# Liquid_Tremolo.net
KiCad netlist of a schematic drawn in Altium Designer
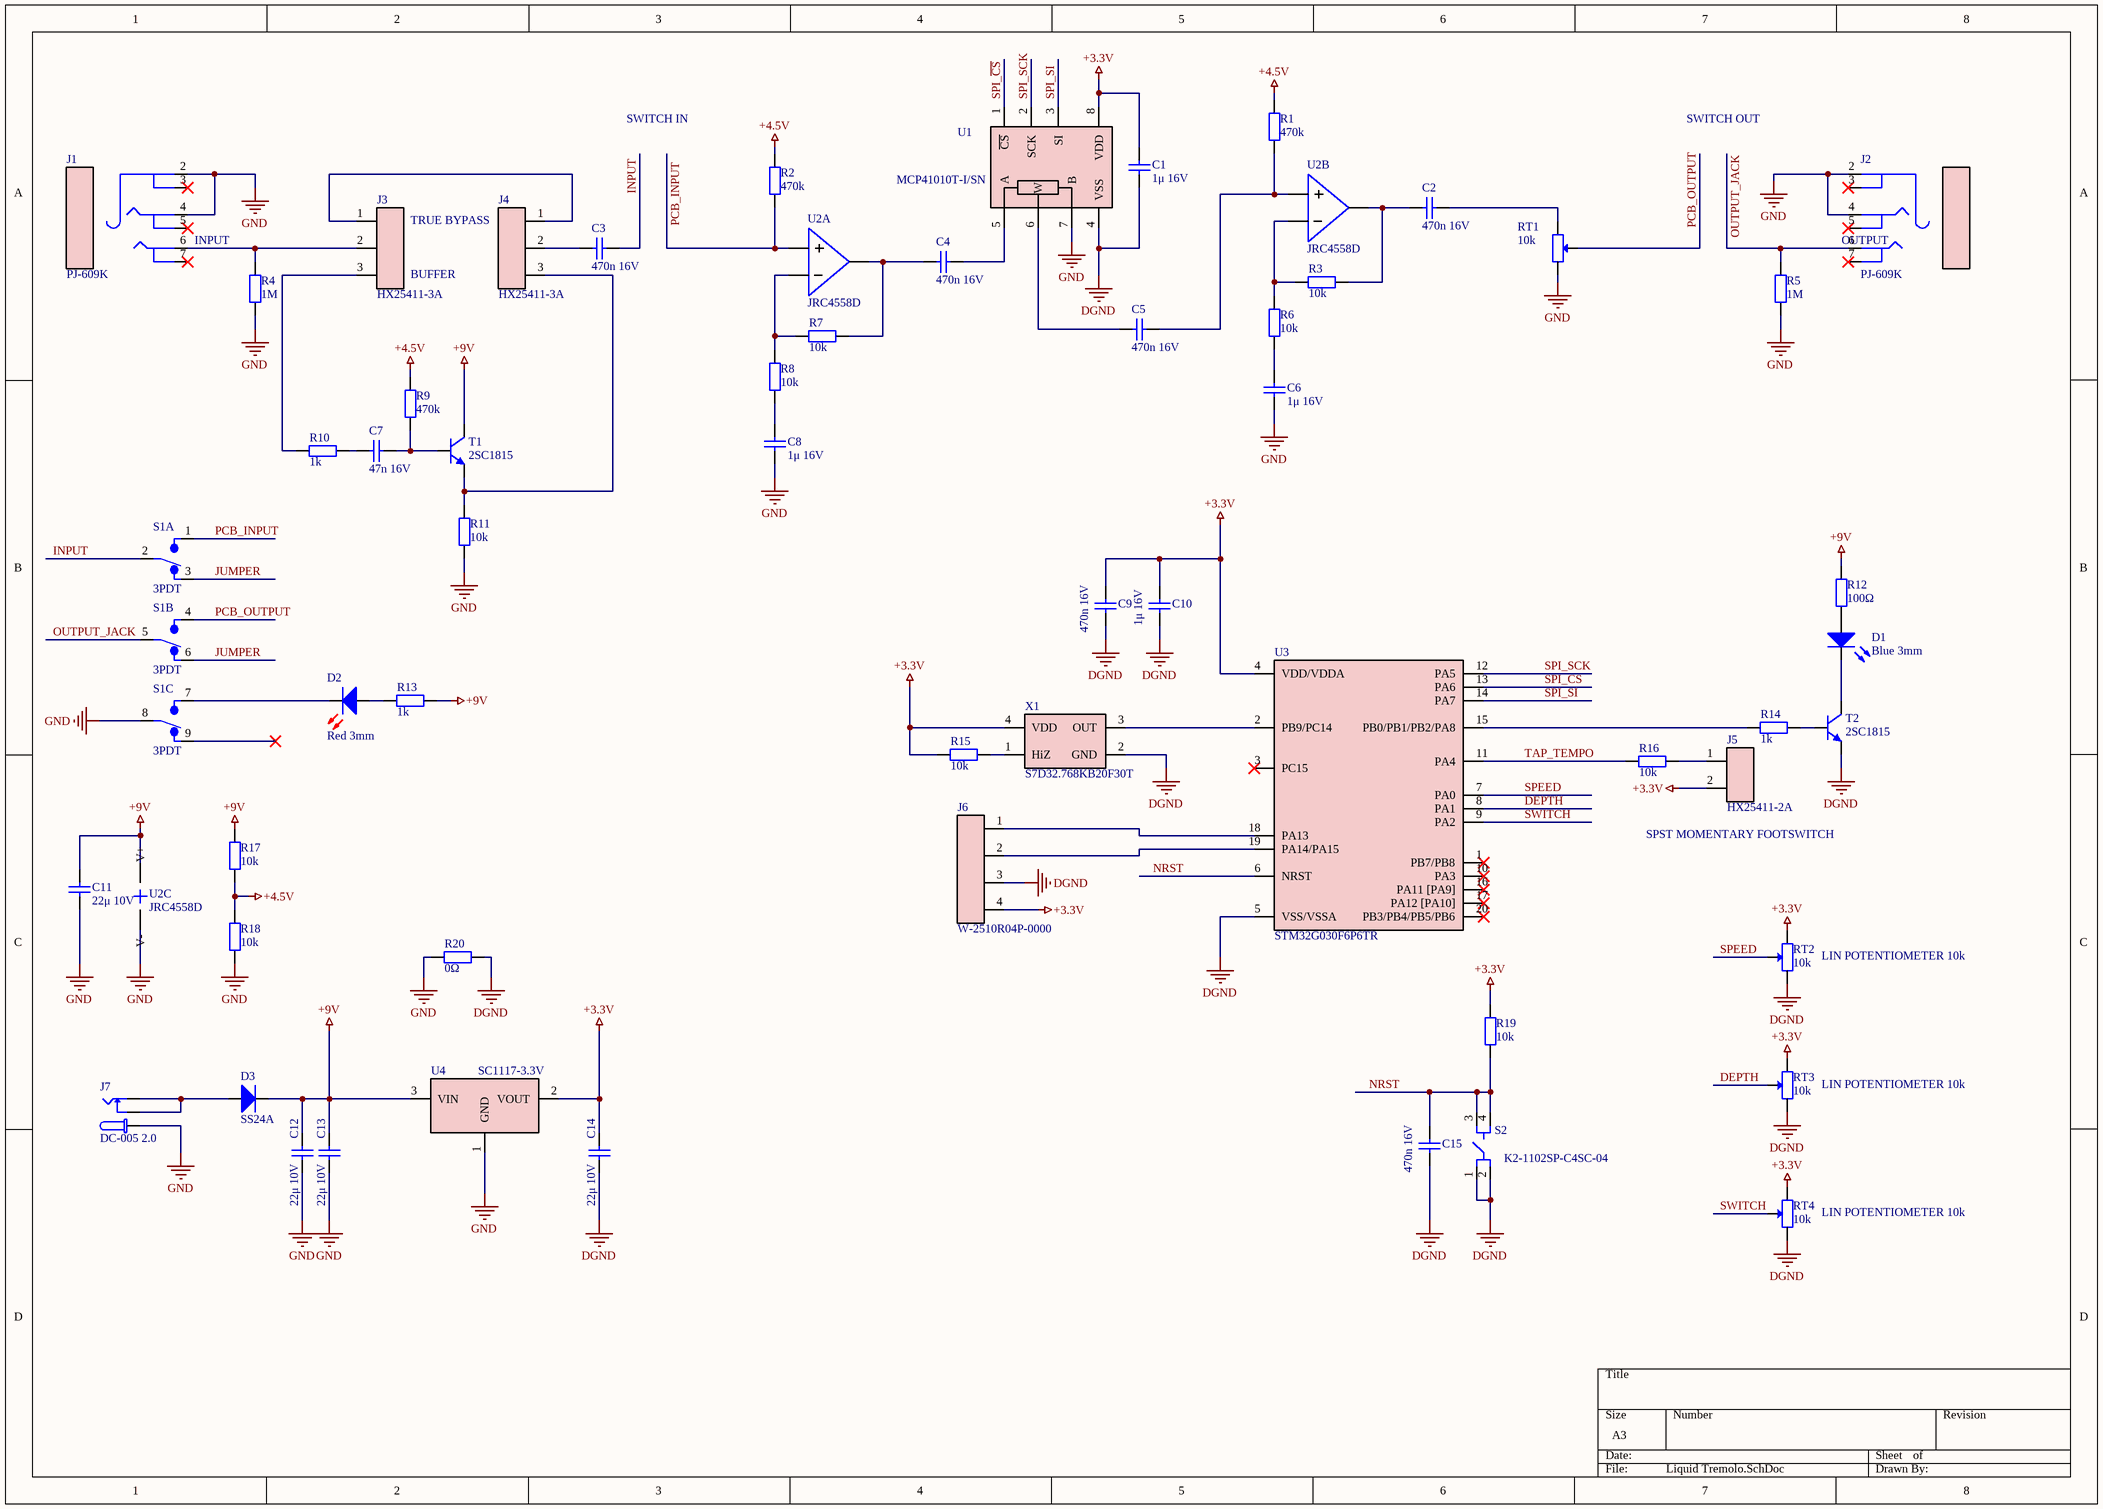
[diagram p0: Liquid Tremolo.SchDoc]

(export (version "E")
  (design (tool "Eeschema 10.0.6"))
  (components
    (comp (ref "C1")
      (value "1μ 16V")
      (footprint "Liquid Tremolo:Capacitor 0603")
      (description "X7R ±10% 1uF 16V 0603 Multilayer Ceramic Capacitors MLCC - SMD/SMT ROHS")
      (fields (field (name "MFR. PART #") "CC0603KRX7R7BB105") (field (name "LCSC PART #") "C106248"))
      (libsource (lib "Liquid Tremolo") (part "Capacitor 1μF 0603 ±10% 16V"))
    )
    (comp (ref "C2")
      (value "470n 16V")
      (footprint "Liquid Tremolo:Capacitor 0603")
      (description "X7R ±10% 470nF 16V 0603 Multilayer Ceramic Capacitors MLCC - SMD/SMT ROHS")
      (fields (field (name "MFR. PART #") "CC0603KRX7R7BB474") (field (name "LCSC PART #") "C106851"))
      (libsource (lib "Liquid Tremolo") (part "Capacitor 470nF 0603 ±10% 16V"))
    )
    (comp (ref "C3")
      (value "470n 16V")
      (footprint "Liquid Tremolo:Capacitor 0603")
      (description "X7R ±10% 470nF 16V 0603 Multilayer Ceramic Capacitors MLCC - SMD/SMT ROHS")
      (fields (field (name "MFR. PART #") "CC0603KRX7R7BB474") (field (name "LCSC PART #") "C106851"))
      (libsource (lib "Liquid Tremolo") (part "Capacitor 470nF 0603 ±10% 16V"))
    )
    (comp (ref "C4")
      (value "470n 16V")
      (footprint "Liquid Tremolo:Capacitor 0603")
      (description "X7R ±10% 470nF 16V 0603 Multilayer Ceramic Capacitors MLCC - SMD/SMT ROHS")
      (fields (field (name "MFR. PART #") "CC0603KRX7R7BB474") (field (name "LCSC PART #") "C106851"))
      (libsource (lib "Liquid Tremolo") (part "Capacitor 470nF 0603 ±10% 16V"))
    )
    (comp (ref "C5")
      (value "470n 16V")
      (footprint "Liquid Tremolo:Capacitor 0603")
      (description "X7R ±10% 470nF 16V 0603 Multilayer Ceramic Capacitors MLCC - SMD/SMT ROHS")
      (fields (field (name "MFR. PART #") "CC0603KRX7R7BB474") (field (name "LCSC PART #") "C106851"))
      (libsource (lib "Liquid Tremolo") (part "Capacitor 470nF 0603 ±10% 16V"))
    )
    (comp (ref "C6")
      (value "1μ 16V")
      (footprint "Liquid Tremolo:Capacitor 0603")
      (description "X7R ±10% 1uF 16V 0603 Multilayer Ceramic Capacitors MLCC - SMD/SMT ROHS")
      (fields (field (name "MFR. PART #") "CC0603KRX7R7BB105") (field (name "LCSC PART #") "C106248"))
      (libsource (lib "Liquid Tremolo") (part "Capacitor 1μF 0603 ±10% 16V"))
    )
    (comp (ref "C7")
      (value "47n 16V")
      (footprint "Liquid Tremolo:Capacitor 0603")
      (description "X7R ±10% 47nF 16V 0603 Multilayer Ceramic Capacitors MLCC - SMD/SMT ROHS")
      (fields (field (name "MFR. PART #") "CC0603KRX7R7BB473") (field (name "LCSC PART #") "C115058"))
      (libsource (lib "Liquid Tremolo") (part "Capacitor 47nF 0603 ±10% 16V"))
    )
    (comp (ref "C8")
      (value "1μ 16V")
      (footprint "Liquid Tremolo:Capacitor 0603")
      (description "X7R ±10% 1uF 16V 0603 Multilayer Ceramic Capacitors MLCC - SMD/SMT ROHS")
      (fields (field (name "MFR. PART #") "CC0603KRX7R7BB105") (field (name "LCSC PART #") "C106248"))
      (libsource (lib "Liquid Tremolo") (part "Capacitor 1μF 0603 ±10% 16V"))
    )
    (comp (ref "C9")
      (value "470n 16V")
      (footprint "Liquid Tremolo:Capacitor 0603")
      (description "X7R ±10% 470nF 16V 0603 Multilayer Ceramic Capacitors MLCC - SMD/SMT ROHS")
      (fields (field (name "MFR. PART #") "CC0603KRX7R7BB474") (field (name "LCSC PART #") "C106851"))
      (libsource (lib "Liquid Tremolo") (part "Capacitor 470nF 0603 ±10% 16V"))
    )
    (comp (ref "C10")
      (value "1μ 16V")
      (footprint "Liquid Tremolo:Capacitor 0603")
      (description "X7R ±10% 1uF 16V 0603 Multilayer Ceramic Capacitors MLCC - SMD/SMT ROHS")
      (fields (field (name "MFR. PART #") "CC0603KRX7R7BB105") (field (name "LCSC PART #") "C106248"))
      (libsource (lib "Liquid Tremolo") (part "Capacitor 1μF 0603 ±10% 16V"))
    )
    (comp (ref "C11")
      (value "22μ 10V")
      (footprint "Liquid Tremolo:Capacitor 0603")
      (description "X5R ±20% 10V 22uF 0603 Multilayer Ceramic Capacitors MLCC - SMD/SMT ROHS")
      (fields (field (name "MFR. PART #") "0603X226M100NT") (field (name "LCSC PART #") "C60077"))
      (libsource (lib "Liquid Tremolo") (part "Capacitor 22μF 0603 ±10% 16V"))
    )
    (comp (ref "C12")
      (value "22μ 10V")
      (footprint "Liquid Tremolo:Capacitor 0603")
      (description "X5R ±20% 10V 22uF 0603 Multilayer Ceramic Capacitors MLCC - SMD/SMT ROHS")
      (fields (field (name "MFR. PART #") "0603X226M100NT") (field (name "LCSC PART #") "C60077"))
      (libsource (lib "Liquid Tremolo") (part "Capacitor 22μF 0603 ±10% 16V"))
    )
    (comp (ref "C13")
      (value "22μ 10V")
      (footprint "Liquid Tremolo:Capacitor 0603")
      (description "X5R ±20% 10V 22uF 0603 Multilayer Ceramic Capacitors MLCC - SMD/SMT ROHS")
      (fields (field (name "MFR. PART #") "0603X226M100NT") (field (name "LCSC PART #") "C60077"))
      (libsource (lib "Liquid Tremolo") (part "Capacitor 22μF 0603 ±10% 16V"))
    )
    (comp (ref "C14")
      (value "22μ 10V")
      (footprint "Liquid Tremolo:Capacitor 0603")
      (description "X5R ±20% 10V 22uF 0603 Multilayer Ceramic Capacitors MLCC - SMD/SMT ROHS")
      (fields (field (name "MFR. PART #") "0603X226M100NT") (field (name "LCSC PART #") "C60077"))
      (libsource (lib "Liquid Tremolo") (part "Capacitor 22μF 0603 ±10% 16V"))
    )
    (comp (ref "C15")
      (value "470n 16V")
      (footprint "Liquid Tremolo:Capacitor 0603")
      (description "X7R ±10% 470nF 16V 0603 Multilayer Ceramic Capacitors MLCC - SMD/SMT ROHS")
      (fields (field (name "MFR. PART #") "CC0603KRX7R7BB474") (field (name "LCSC PART #") "C106851"))
      (libsource (lib "Liquid Tremolo") (part "Capacitor 470nF 0603 ±10% 16V"))
    )
    (comp (ref "D1")
      (value "Blue 3mm")
      (footprint "Liquid Tremolo:LED 3MM BLUE")
      (description "Blue 460nm~470nm 2.7V~3.6V Through Hole Light Emitting Diodes (LED) ROHS")
      (fields (field (name "MFR. PART #") "TJ-L3FYTGCBMCGSFLC6B-A5") (field (name "LCSC PART #") "C330760"))
      (libsource (lib "Liquid Tremolo") (part "Diode LED Blue 3mm THT"))
    )
    (comp (ref "D2")
      (value "Red 3mm")
      (footprint "Liquid Tremolo:LED 3MM BLUE")
      (description "Red 620nm~630nm 1.8V~2.6V Through Hole Light Emitting Diodes (LED) ROHS")
      (fields (field (name "MFR. PART #") "TJ-L4FYTGCRMFCSFLC2R-A5") (field (name "LCSC PART #") "C331039"))
      (libsource (lib "Liquid Tremolo") (part "Diode LED Red 3mm THT"))
    )
    (comp (ref "D3")
      (value "SS24A")
      (footprint "Liquid Tremolo:SS24A")
      (description "40V 2A 500mV @ 2A SMA(DO-214AC) Schottky Barrier Diodes (SBD) ROHS")
      (fields (field (name "LCSC PART #") "C181203"))
      (libsource (lib "Liquid Tremolo") (part "Diode 40V 2A 500mV SS24A"))
    )
    (comp (ref "J1")
      (value "PJ-609K")
      (footprint "Liquid Tremolo:HOOYA PJ-609K")
      (description "6.35mm Plug-in headphone holder Horizontal 6 Female - Audio & Video Connectors ROHS")
      (fields (field (name "LCSC PART #") "C309276"))
      (libsource (lib "Liquid Tremolo") (part "Mechanical Connector JACK 6.35mm PJ-609K"))
    )
    (comp (ref "J2")
      (value "PJ-609K")
      (footprint "Liquid Tremolo:HOOYA PJ-609K")
      (description "6.35mm Plug-in headphone holder Horizontal 6 Female - Audio & Video Connectors ROHS")
      (fields (field (name "LCSC PART #") "C309276"))
      (libsource (lib "") (part "Mechanical Connector JACK 6.35mm PJ-609K_1"))
    )
    (comp (ref "J3")
      (value "HX25411-3A")
      (footprint "Liquid Tremolo:HX25411-3A")
      (description "3 Header CH 0.100\"(2.54mm) Male Pin Through Hole Wire To Board / Wire To Wire Connector ROHS")
      (fields (field (name "LCSC PART #") "C190647"))
      (libsource (lib "") (part "Mechanical Connector 3P 2.54mm THT HX25411-3A_1"))
    )
    (comp (ref "J4")
      (value "HX25411-3A")
      (footprint "Liquid Tremolo:HX25411-3A")
      (description "3 Header CH 0.100\"(2.54mm) Male Pin Through Hole Wire To Board / Wire To Wire Connector ROHS")
      (fields (field (name "LCSC PART #") "C190647"))
      (libsource (lib "Liquid Tremolo") (part "Mechanical Connector 3P 2.54mm THT HX25411-3A"))
    )
    (comp (ref "J5")
      (value "HX25411-2A")
      (footprint "Liquid Tremolo:HX25411-2A")
      (description "LCSC Part # C181912\r\nPackage P=2.54mm\r\nManufacturer HX(Zhejiang Yueqing Hongxing Elec)")
      (fields (field (name "LCSC PART #") "C181912"))
      (libsource (lib "Liquid Tremolo") (part "Mechanical Connector 2P 2.54mm THT HX25411-2A"))
    )
    (comp (ref "J6")
      (value "W-2510R04P-0000")
      (footprint "Liquid Tremolo:W-2510R04P-0000")
      (fields (field (name "LCSC PART #") "C169027"))
      (libsource (lib "Liquid Tremolo") (part "Mechanical Connector 4P 2.54mm THT Right Angle W-2510R04P-0000"))
    )
    (comp (ref "J7")
      (value "DC-005 2.0")
      (footprint "Liquid Tremolo:DC-005 2.0")
      (description "Through Hole AC/DC Power Plugs & Receptacles ROHS")
      (fields (field (name "LCSC PART #") "C16214"))
      (libsource (lib "Liquid Tremolo") (part "Mechanical DC Jack DC-005 2.0"))
    )
    (comp (ref "R1")
      (value "470k")
      (footprint "Liquid Tremolo:Resistor 0603")
      (description "±1% 470kΩ ±100ppm/℃ 0.1W 0603 Chip Resistor - Surface Mount ROHS")
      (fields (field (name "MFR. PART #") "0603WAF4703T5E") (field (name "LCSC PART #") "C23178"))
      (libsource (lib "Liquid Tremolo") (part "Resistor 470kΩ 0603 ±1% 0.1W"))
    )
    (comp (ref "R2")
      (value "470k")
      (footprint "Liquid Tremolo:Resistor 0603")
      (description "±1% 470kΩ ±100ppm/℃ 0.1W 0603 Chip Resistor - Surface Mount ROHS")
      (fields (field (name "MFR. PART #") "0603WAF4703T5E") (field (name "LCSC PART #") "C23178"))
      (libsource (lib "Liquid Tremolo") (part "Resistor 470kΩ 0603 ±1% 0.1W"))
    )
    (comp (ref "R3")
      (value "10k")
      (footprint "Liquid Tremolo:Resistor 0603")
      (description "±1% ±100ppm/℃ 10kΩ 0.1W 0603 Chip Resistor - Surface Mount ROHS")
      (fields (field (name "MFR. PART #") "0603WAF1002T5E") (field (name "LCSC PART #") "C25804"))
      (libsource (lib "Liquid Tremolo") (part "Resistor 10kΩ 0603 ±1% 0.1W"))
    )
    (comp (ref "R4")
      (value "1M")
      (footprint "Liquid Tremolo:Resistor 0603")
      (description "1MΩ ±1% 0.1W 0603 Chip Resistor - Surface Mount ROHS")
      (fields (field (name "MFR. PART #") "RMC06031M1%N") (field (name "LCSC PART #") "C269705"))
      (libsource (lib "Liquid Tremolo") (part "Resistor 1MΩ 0603 ±1% 0.1W"))
    )
    (comp (ref "R5")
      (value "1M")
      (footprint "Liquid Tremolo:Resistor 0603")
      (description "1MΩ ±1% 0.1W 0603 Chip Resistor - Surface Mount ROHS")
      (fields (field (name "MFR. PART #") "RMC06031M1%N") (field (name "LCSC PART #") "C269705"))
      (libsource (lib "") (part "Resistor 1MΩ 0603 ±1% 0.1W_1"))
    )
    (comp (ref "R6")
      (value "10k")
      (footprint "Liquid Tremolo:Resistor 0603")
      (description "±1% ±100ppm/℃ 10kΩ 0.1W 0603 Chip Resistor - Surface Mount ROHS")
      (fields (field (name "MFR. PART #") "0603WAF1002T5E") (field (name "LCSC PART #") "C25804"))
      (libsource (lib "") (part "Resistor 10kΩ 0603 ±1% 0.1W_1"))
    )
    (comp (ref "R7")
      (value "10k")
      (footprint "Liquid Tremolo:Resistor 0603")
      (description "±1% ±100ppm/℃ 10kΩ 0.1W 0603 Chip Resistor - Surface Mount ROHS")
      (fields (field (name "MFR. PART #") "0603WAF1002T5E") (field (name "LCSC PART #") "C25804"))
      (libsource (lib "Liquid Tremolo") (part "Resistor 10kΩ 0603 ±1% 0.1W"))
    )
    (comp (ref "R8")
      (value "10k")
      (footprint "Liquid Tremolo:Resistor 0603")
      (description "±1% ±100ppm/℃ 10kΩ 0.1W 0603 Chip Resistor - Surface Mount ROHS")
      (fields (field (name "MFR. PART #") "0603WAF1002T5E") (field (name "LCSC PART #") "C25804"))
      (libsource (lib "") (part "Resistor 10kΩ 0603 ±1% 0.1W_1"))
    )
    (comp (ref "R9")
      (value "470k")
      (footprint "Liquid Tremolo:Resistor 0603")
      (description "±1% 470kΩ ±100ppm/℃ 0.1W 0603 Chip Resistor - Surface Mount ROHS")
      (fields (field (name "MFR. PART #") "0603WAF4703T5E") (field (name "LCSC PART #") "C23178"))
      (libsource (lib "Liquid Tremolo") (part "Resistor 470kΩ 0603 ±1% 0.1W"))
    )
    (comp (ref "R10")
      (value "1k")
      (footprint "Liquid Tremolo:Resistor 0603")
      (description "±1% ±100ppm/℃ 1kΩ 0.1W 0603 Chip Resistor - Surface Mount ROHS")
      (fields (field (name "MFR. PART #") "RC0603FR-071KL") (field (name "LCSC PART #") "C22548"))
      (libsource (lib "Liquid Tremolo") (part "Resistor 1kΩ 0603 ±1% 0.1W"))
    )
    (comp (ref "R11")
      (value "10k")
      (footprint "Liquid Tremolo:Resistor 0603")
      (description "±1% ±100ppm/℃ 10kΩ 0.1W 0603 Chip Resistor - Surface Mount ROHS")
      (fields (field (name "MFR. PART #") "0603WAF1002T5E") (field (name "LCSC PART #") "C25804"))
      (libsource (lib "") (part "Resistor 10kΩ 0603 ±1% 0.1W_1"))
    )
    (comp (ref "R12")
      (value "100Ω")
      (footprint "Liquid Tremolo:Resistor 0603")
      (description "±1% ±200ppm/℃ 100Ω 0.1W 0603 Chip Resistor - Surface Mount ROHS")
      (fields (field (name "MFR. PART #") "0603WAF1000T5E") (field (name "LCSC PART #") "C22775"))
      (libsource (lib "Liquid Tremolo") (part "Resistor 100Ω 0603 ±1% 0.1W"))
    )
    (comp (ref "R13")
      (value "1k")
      (footprint "Liquid Tremolo:Resistor 0603")
      (description "±1% ±100ppm/℃ 1kΩ 0.1W 0603 Chip Resistor - Surface Mount ROHS")
      (fields (field (name "MFR. PART #") "RC0603FR-071KL") (field (name "LCSC PART #") "C22548"))
      (libsource (lib "Liquid Tremolo") (part "Resistor 1kΩ 0603 ±1% 0.1W"))
    )
    (comp (ref "R14")
      (value "1k")
      (footprint "Liquid Tremolo:Resistor 0603")
      (description "±1% ±100ppm/℃ 1kΩ 0.1W 0603 Chip Resistor - Surface Mount ROHS")
      (fields (field (name "MFR. PART #") "RC0603FR-071KL") (field (name "LCSC PART #") "C22548"))
      (libsource (lib "Liquid Tremolo") (part "Resistor 1kΩ 0603 ±1% 0.1W"))
    )
    (comp (ref "R15")
      (value "10k")
      (footprint "Liquid Tremolo:Resistor 0603")
      (description "±1% ±100ppm/℃ 10kΩ 0.1W 0603 Chip Resistor - Surface Mount ROHS")
      (fields (field (name "MFR. PART #") "0603WAF1002T5E") (field (name "LCSC PART #") "C25804"))
      (libsource (lib "") (part "Resistor 10kΩ 0603 ±1% 0.1W_2"))
    )
    (comp (ref "R16")
      (value "10k")
      (footprint "Liquid Tremolo:Resistor 0603")
      (description "±1% ±100ppm/℃ 10kΩ 0.1W 0603 Chip Resistor - Surface Mount ROHS")
      (fields (field (name "MFR. PART #") "0603WAF1002T5E") (field (name "LCSC PART #") "C25804"))
      (libsource (lib "") (part "Resistor 10kΩ 0603 ±1% 0.1W_2"))
    )
    (comp (ref "R17")
      (value "10k")
      (footprint "Liquid Tremolo:Resistor 0603")
      (description "±1% ±100ppm/℃ 10kΩ 0.1W 0603 Chip Resistor - Surface Mount ROHS")
      (fields (field (name "MFR. PART #") "0603WAF1002T5E") (field (name "LCSC PART #") "C25804"))
      (libsource (lib "") (part "Resistor 10kΩ 0603 ±1% 0.1W_1"))
    )
    (comp (ref "R18")
      (value "10k")
      (footprint "Liquid Tremolo:Resistor 0603")
      (description "±1% ±100ppm/℃ 10kΩ 0.1W 0603 Chip Resistor - Surface Mount ROHS")
      (fields (field (name "MFR. PART #") "0603WAF1002T5E") (field (name "LCSC PART #") "C25804"))
      (libsource (lib "") (part "Resistor 10kΩ 0603 ±1% 0.1W_1"))
    )
    (comp (ref "R19")
      (value "10k")
      (footprint "Liquid Tremolo:Resistor 0603")
      (description "±1% ±100ppm/℃ 10kΩ 0.1W 0603 Chip Resistor - Surface Mount ROHS")
      (fields (field (name "MFR. PART #") "0603WAF1002T5E") (field (name "LCSC PART #") "C25804"))
      (libsource (lib "") (part "Resistor 10kΩ 0603 ±1% 0.1W_1"))
    )
    (comp (ref "R20")
      (value "0Ω")
      (footprint "Liquid Tremolo:Resistor 0603")
      (description "75V -55℃~+155℃ ±1% Thick Film Resistors 100mW 0Ω 0603 Chip Resistor - Surface Mount ROHS")
      (fields (field (name "MFR. PART #") "RC0603FR-070RL") (field (name "LCSC PART #") "C100044"))
      (libsource (lib "Liquid Tremolo") (part "Resistor 0Ω 0603 ±1% 0.1W"))
    )
    (comp (ref "RT1")
      (value "10k")
      (footprint "Liquid Tremolo:RK09D1130C2P")
      (description "±20% 10kΩ Plugin Variable Resistors/Potentiometers ROHS")
      (fields (field (name "MFR. PART #") "RK09D1130C2P") (field (name "LCSC PART #") "C361173"))
      (libsource (lib "") (part "Potentiometer 10kΩ plugin ±20% RK09D1130C2P_1"))
    )
    (comp (ref "RT2")
      (value "10k")
      (footprint "Liquid Tremolo:RK09D1130C2P")
      (description "±20% 10kΩ Plugin Variable Resistors/Potentiometers ROHS")
      (fields (field (name "MFR. PART #") "RK09D1130C2P") (field (name "LCSC PART #") "C361173"))
      (libsource (lib "Liquid Tremolo") (part "Potentiometer 10kΩ plugin ±20% RK09D1130C2P"))
    )
    (comp (ref "RT3")
      (value "10k")
      (footprint "Liquid Tremolo:RK09D1130C2P")
      (description "±20% 10kΩ Plugin Variable Resistors/Potentiometers ROHS")
      (fields (field (name "MFR. PART #") "RK09D1130C2P") (field (name "LCSC PART #") "C361173"))
      (libsource (lib "Liquid Tremolo") (part "Potentiometer 10kΩ plugin ±20% RK09D1130C2P"))
    )
    (comp (ref "RT4")
      (value "10k")
      (footprint "Liquid Tremolo:RK09D1130C2P")
      (description "±20% 10kΩ Plugin Variable Resistors/Potentiometers ROHS")
      (fields (field (name "MFR. PART #") "RK09D1130C2P") (field (name "LCSC PART #") "C361173"))
      (libsource (lib "Liquid Tremolo") (part "Potentiometer 10kΩ plugin ±20% RK09D1130C2P"))
    )
    (comp (ref "S1")
      (value "3PDT")
      (footprint "Liquid Tremolo:3PDT")
      (description "Top Actuated 50mA @ 12VDC Round Button SPST 6*6mm Tactile Switches ROHS")
      (libsource (lib "Liquid Tremolo") (part "Mechanical 3PDT Footswitch"))
    )
    (comp (ref "S2")
      (value "K2-1102SP-C4SC-04")
      (footprint "Liquid Tremolo:K2-1102SP-C4SC-04")
      (description "Top Actuated 50mA @ 12VDC Round Button SPST 6*6mm Tactile Switches ROHS")
      (fields (field (name "LCSC PART #") "C127509"))
      (libsource (lib "Liquid Tremolo") (part "Mechanical Tactile Switch 6x6mm SMD"))
    )
    (comp (ref "T1")
      (value "2SC1815")
      (footprint "Liquid Tremolo:2SC1815")
      (description "50V 0.2W 0.15A NPN SOT-23(SOT-23-3) Bipolar Transistors - BJT ROHS")
      (fields (field (name "LCSC PART #") "C181171"))
      (libsource (lib "Liquid Tremolo") (part "Transistor 2SC1815 50V 0.2W 0.15A NPN SOT-23"))
    )
    (comp (ref "T2")
      (value "2SC1815")
      (footprint "Liquid Tremolo:2SC1815")
      (description "50V 0.2W 0.15A NPN SOT-23(SOT-23-3) Bipolar Transistors - BJT ROHS")
      (fields (field (name "LCSC PART #") "C181171"))
      (libsource (lib "Liquid Tremolo") (part "Transistor 2SC1815 50V 0.2W 0.15A NPN SOT-23"))
    )
    (comp (ref "U1")
      (value "MCP41010T-I/SN")
      (footprint "Liquid Tremolo:MCP41010")
      (description "SOIC-8 Digital Potentiometers ROHS")
      (fields (field (name "LCSC PART #") "C136395"))
      (libsource (lib "Liquid Tremolo") (part "IC Digital Potentiometer SOIC-8 MCP41010T-I/SN"))
    )
    (comp (ref "U2")
      (value "JRC4558D")
      (footprint "Liquid Tremolo:JRC4558")
      (description "SOP-8 Operational Amplifier ROHS")
      (fields (field (name "LCSC PART #") "C443686"))
      (libsource (lib "Liquid Tremolo") (part "IC OP-AMP JRC4558D SOP-8"))
    )
    (comp (ref "U3")
      (value "STM32G030F6P6TR")
      (footprint "Liquid Tremolo:STM32G030F6P6TR")
      (description "TSSOP-20 ST Microelectronics ROHS")
      (fields (field (name "LCSC PART #") "C529330"))
      (libsource (lib "Liquid Tremolo") (part "IC MCU STM32G030F6P6TR TSSOP-20"))
    )
    (comp (ref "U4")
      (value "SC1117-3.3V")
      (footprint "Liquid Tremolo:SC1117-3.3V")
      (description "12V 1.5V @ 700mA Fixed 3.3V SOT-223 Linear Voltage Regulators (LDO) ROHS")
      (fields (field (name "LCSC PART #") "C173386"))
      (libsource (lib "Liquid Tremolo") (part "IC LDO 3.3V Fixed 700mA SOT-223 SC1117-3.3V"))
    )
    (comp (ref "X1")
      (value "S7D32.768KB20F30T")
      (footprint "Liquid Tremolo:S7D32.768KB20F30T")
      (description "3.3V 32.768KHz ±20ppm SMD7050-4P Oscillators ROHS")
      (fields (field (name "LCSC PART #") "C387070"))
      (libsource (lib "Liquid Tremolo") (part "Crystal Oscillator 32.768kHz S7D32.768KB20F30T"))
    )
  )
  (nets
    (net (code "1") (name "+3.3V") (class "Default")
      (node (ref "C1") (pin "1") (pinfunction "1_1") (pintype "passive"))
      (node (ref "C10") (pin "2") (pinfunction "2_2") (pintype "passive"))
      (node (ref "C14") (pin "2") (pinfunction "2_2") (pintype "passive"))
      (node (ref "C9") (pin "2") (pinfunction "2_2") (pintype "passive"))
      (node (ref "J5") (pin "2") (pinfunction "2_2") (pintype "passive"))
      (node (ref "J6") (pin "4") (pinfunction "4_4") (pintype "passive"))
      (node (ref "R15") (pin "1") (pinfunction "1_1") (pintype "passive"))
      (node (ref "R19") (pin "2") (pinfunction "2_2") (pintype "passive"))
      (node (ref "RT2") (pin "1") (pinfunction "1_1") (pintype "passive"))
      (node (ref "RT3") (pin "1") (pinfunction "1_1") (pintype "passive"))
      (node (ref "RT4") (pin "1") (pinfunction "1_1") (pintype "passive"))
      (node (ref "U1") (pin "8") (pinfunction "VDD_8") (pintype "passive"))
      (node (ref "U3") (pin "4") (pinfunction "VDD/VDDA_4") (pintype "passive"))
      (node (ref "U4") (pin "2") (pinfunction "VOUT_2") (pintype "passive"))
      (node (ref "X1") (pin "4") (pinfunction "VDD_4") (pintype "passive"))
    )
    (net (code "2") (name "+4.5V") (class "Default")
      (node (ref "R1") (pin "2") (pinfunction "2_2") (pintype "passive"))
      (node (ref "R17") (pin "1") (pinfunction "1_1") (pintype "passive"))
      (node (ref "R18") (pin "2") (pinfunction "2_2") (pintype "passive"))
      (node (ref "R2") (pin "2") (pinfunction "2_2") (pintype "passive"))
      (node (ref "R9") (pin "2") (pinfunction "2_2") (pintype "passive"))
    )
    (net (code "3") (name "+9V") (class "Default")
      (node (ref "C11") (pin "2") (pinfunction "2_2") (pintype "passive"))
      (node (ref "C12") (pin "2") (pinfunction "2_2") (pintype "passive"))
      (node (ref "C13") (pin "2") (pinfunction "2_2") (pintype "passive"))
      (node (ref "D3") (pin "2") (pinfunction "2_2") (pintype "passive"))
      (node (ref "R12") (pin "2") (pinfunction "2_2") (pintype "passive"))
      (node (ref "R13") (pin "2") (pinfunction "2_2") (pintype "passive"))
      (node (ref "R17") (pin "2") (pinfunction "2_2") (pintype "passive"))
      (node (ref "T1") (pin "3") (pinfunction "C_3") (pintype "passive"))
      (node (ref "U2") (pin "8") (pinfunction "V+_8") (pintype "passive"))
      (node (ref "U4") (pin "3") (pinfunction "VIN_3") (pintype "passive"))
    )
    (net (code "4") (name "/DEPTH") (class "Default")
      (node (ref "RT3") (pin "2") (pinfunction "2_2") (pintype "passive"))
      (node (ref "U3") (pin "8") (pinfunction "PA1_8") (pintype "passive"))
    )
    (net (code "5") (name "/INPUT") (class "Default")
      (node (ref "C3") (pin "2") (pinfunction "2_2") (pintype "passive"))
      (node (ref "S1") (pin "2") (pinfunction "2_2") (pintype "passive"))
    )
    (net (code "6") (name "/JUMPER") (class "Default")
      (node (ref "S1") (pin "3") (pinfunction "3_3") (pintype "passive"))
      (node (ref "S1") (pin "6") (pinfunction "6_6") (pintype "passive"))
    )
    (net (code "7") (name "/NRST") (class "Default")
      (node (ref "C15") (pin "2") (pinfunction "2_2") (pintype "passive"))
      (node (ref "R19") (pin "1") (pinfunction "1_1") (pintype "passive"))
      (node (ref "S2") (pin "3") (pinfunction "3_3") (pintype "passive"))
      (node (ref "S2") (pin "4") (pinfunction "4_4") (pintype "passive"))
      (node (ref "U3") (pin "6") (pinfunction "NRST_6") (pintype "passive"))
    )
    (net (code "8") (name "/OUTPUT_JACK") (class "Default")
      (node (ref "J2") (pin "6") (pinfunction "6_6") (pintype "passive"))
      (node (ref "R5") (pin "2") (pinfunction "2_2") (pintype "passive"))
      (node (ref "S1") (pin "5") (pinfunction "5_5") (pintype "passive"))
    )
    (net (code "9") (name "/PCB_INPUT") (class "Default")
      (node (ref "R2") (pin "1") (pinfunction "1_1") (pintype "passive"))
      (node (ref "S1") (pin "1") (pinfunction "1_1") (pintype "passive"))
      (node (ref "U2") (pin "3") (pinfunction "IN+_3") (pintype "passive"))
    )
    (net (code "10") (name "/PCB_OUTPUT") (class "Default")
      (node (ref "RT1") (pin "2") (pinfunction "2_2") (pintype "passive"))
      (node (ref "S1") (pin "4") (pinfunction "4_4") (pintype "passive"))
    )
    (net (code "11") (name "/SPEED") (class "Default")
      (node (ref "RT2") (pin "2") (pinfunction "2_2") (pintype "passive"))
      (node (ref "U3") (pin "7") (pinfunction "PA0_7") (pintype "passive"))
    )
    (net (code "12") (name "/SPI_SCK") (class "Default")
      (node (ref "U1") (pin "2") (pinfunction "SCK_2") (pintype "passive"))
      (node (ref "U3") (pin "12") (pinfunction "PA5_12") (pintype "passive"))
    )
    (net (code "13") (name "/SPI_SI") (class "Default")
      (node (ref "U1") (pin "3") (pinfunction "SI_3") (pintype "passive"))
      (node (ref "U3") (pin "14") (pinfunction "PA7_14") (pintype "passive"))
    )
    (net (code "14") (name "/SPI_~{CS}") (class "Default")
      (node (ref "U1") (pin "1") (pinfunction "~{CS}_1") (pintype "passive"))
      (node (ref "U3") (pin "13") (pinfunction "PA6_13") (pintype "passive"))
    )
    (net (code "15") (name "/SWITCH") (class "Default")
      (node (ref "RT4") (pin "2") (pinfunction "2_2") (pintype "passive"))
      (node (ref "U3") (pin "9") (pinfunction "PA2_9") (pintype "passive"))
    )
    (net (code "16") (name "/TAP_TEMPO") (class "Default")
      (node (ref "R16") (pin "1") (pinfunction "1_1") (pintype "passive"))
      (node (ref "U3") (pin "11") (pinfunction "PA4_11") (pintype "passive"))
    )
    (net (code "17") (name "DGND") (class "Default")
      (node (ref "C1") (pin "2") (pinfunction "2_2") (pintype "passive"))
      (node (ref "C10") (pin "1") (pinfunction "1_1") (pintype "passive"))
      (node (ref "C14") (pin "1") (pinfunction "1_1") (pintype "passive"))
      (node (ref "C15") (pin "1") (pinfunction "1_1") (pintype "passive"))
      (node (ref "C9") (pin "1") (pinfunction "1_1") (pintype "passive"))
      (node (ref "J6") (pin "3") (pinfunction "3_3") (pintype "passive"))
      (node (ref "R20") (pin "2") (pinfunction "2_2") (pintype "passive"))
      (node (ref "RT2") (pin "3") (pinfunction "3_3") (pintype "passive"))
      (node (ref "RT3") (pin "3") (pinfunction "3_3") (pintype "passive"))
      (node (ref "RT4") (pin "3") (pinfunction "3_3") (pintype "passive"))
      (node (ref "S2") (pin "1") (pinfunction "1_1") (pintype "passive"))
      (node (ref "S2") (pin "2") (pinfunction "2_2") (pintype "passive"))
      (node (ref "T2") (pin "2") (pinfunction "E_2") (pintype "passive"))
      (node (ref "U1") (pin "4") (pinfunction "VSS_4") (pintype "passive"))
      (node (ref "U3") (pin "5") (pinfunction "VSS/VSSA_5") (pintype "passive"))
      (node (ref "X1") (pin "2") (pinfunction "GND_2") (pintype "passive"))
    )
    (net (code "18") (name "GND") (class "Default")
      (node (ref "C11") (pin "1") (pinfunction "1_1") (pintype "passive"))
      (node (ref "C12") (pin "1") (pinfunction "1_1") (pintype "passive"))
      (node (ref "C13") (pin "1") (pinfunction "1_1") (pintype "passive"))
      (node (ref "C6") (pin "1") (pinfunction "1_1") (pintype "passive"))
      (node (ref "C8") (pin "1") (pinfunction "1_1") (pintype "passive"))
      (node (ref "J1") (pin "2") (pinfunction "2_2") (pintype "passive"))
      (node (ref "J1") (pin "4") (pinfunction "4_4") (pintype "passive"))
      (node (ref "J2") (pin "2") (pinfunction "2_2") (pintype "passive"))
      (node (ref "J2") (pin "4") (pinfunction "4_4") (pintype "passive"))
      (node (ref "J7") (pin "4") (pinfunction "4_4") (pintype "passive"))
      (node (ref "R11") (pin "1") (pinfunction "1_1") (pintype "passive"))
      (node (ref "R18") (pin "1") (pinfunction "1_1") (pintype "passive"))
      (node (ref "R20") (pin "1") (pinfunction "1_1") (pintype "passive"))
      (node (ref "R4") (pin "1") (pinfunction "1_1") (pintype "passive"))
      (node (ref "R5") (pin "1") (pinfunction "1_1") (pintype "passive"))
      (node (ref "RT1") (pin "3") (pinfunction "3_3") (pintype "passive"))
      (node (ref "S1") (pin "8") (pinfunction "8_8") (pintype "passive"))
      (node (ref "U1") (pin "7") (pinfunction "B_7") (pintype "passive"))
      (node (ref "U2") (pin "4") (pinfunction "V-_4") (pintype "passive"))
      (node (ref "U4") (pin "1") (pinfunction "GND_1") (pintype "passive"))
    )
    (net (code "19") (name "Net-(C2-Pad2)") (class "Default")
      (node (ref "C2") (pin "2") (pinfunction "2_2") (pintype "passive"))
      (node (ref "RT1") (pin "1") (pinfunction "1_1") (pintype "passive"))
    )
    (net (code "20") (name "Net-(C3-Pad1)") (class "Default")
      (node (ref "C3") (pin "1") (pinfunction "1_1") (pintype "passive"))
      (node (ref "J4") (pin "2") (pinfunction "2_2") (pintype "passive"))
    )
    (net (code "21") (name "Net-(C6-Pad2)") (class "Default")
      (node (ref "C6") (pin "2") (pinfunction "2_2") (pintype "passive"))
      (node (ref "R6") (pin "1") (pinfunction "1_1") (pintype "passive"))
    )
    (net (code "22") (name "Net-(C7-Pad1)") (class "Default")
      (node (ref "C7") (pin "1") (pinfunction "1_1") (pintype "passive"))
      (node (ref "R10") (pin "2") (pinfunction "2_2") (pintype "passive"))
    )
    (net (code "23") (name "Net-(C8-Pad2)") (class "Default")
      (node (ref "C8") (pin "2") (pinfunction "2_2") (pintype "passive"))
      (node (ref "R8") (pin "1") (pinfunction "1_1") (pintype "passive"))
    )
    (net (code "24") (name "Net-(D1-Pad2)") (class "Default")
      (node (ref "D1") (pin "2") (pinfunction "2_2") (pintype "passive"))
      (node (ref "R12") (pin "1") (pinfunction "1_1") (pintype "passive"))
    )
    (net (code "25") (name "Net-(D2-Pad1)") (class "Default")
      (node (ref "D2") (pin "1") (pinfunction "1_1") (pintype "passive"))
      (node (ref "S1") (pin "7") (pinfunction "7_7") (pintype "passive"))
    )
    (net (code "26") (name "Net-(D2-Pad2)") (class "Default")
      (node (ref "D2") (pin "2") (pinfunction "2_2") (pintype "passive"))
      (node (ref "R13") (pin "1") (pinfunction "1_1") (pintype "passive"))
    )
    (net (code "27") (name "Net-(D3-Pad1)") (class "Default")
      (node (ref "D3") (pin "1") (pinfunction "1_1") (pintype "passive"))
      (node (ref "J7") (pin "2") (pinfunction "2_2") (pintype "passive"))
      (node (ref "J7") (pin "3") (pinfunction "3_3") (pintype "passive"))
    )
    (net (code "28") (name "Net-(J1-Pad6)") (class "Default")
      (node (ref "J1") (pin "6") (pinfunction "6_6") (pintype "passive"))
      (node (ref "J3") (pin "2") (pinfunction "2_2") (pintype "passive"))
      (node (ref "R4") (pin "2") (pinfunction "2_2") (pintype "passive"))
    )
    (net (code "29") (name "Net-(J3-Pad1)") (class "Default")
      (node (ref "J3") (pin "1") (pinfunction "1_1") (pintype "passive"))
      (node (ref "J4") (pin "1") (pinfunction "1_1") (pintype "passive"))
    )
    (net (code "30") (name "Net-(J3-Pad3)") (class "Default")
      (node (ref "J3") (pin "3") (pinfunction "3_3") (pintype "passive"))
      (node (ref "R10") (pin "1") (pinfunction "1_1") (pintype "passive"))
    )
    (net (code "31") (name "Net-(J5-Pad1)") (class "Default")
      (node (ref "J5") (pin "1") (pinfunction "1_1") (pintype "passive"))
      (node (ref "R16") (pin "2") (pinfunction "2_2") (pintype "passive"))
    )
    (net (code "32") (name "Net-(T1-B)") (class "Default")
      (node (ref "C7") (pin "2") (pinfunction "2_2") (pintype "passive"))
      (node (ref "R9") (pin "1") (pinfunction "1_1") (pintype "passive"))
      (node (ref "T1") (pin "1") (pinfunction "B_1") (pintype "passive"))
    )
    (net (code "33") (name "Net-(T1-E)") (class "Default")
      (node (ref "J4") (pin "3") (pinfunction "3_3") (pintype "passive"))
      (node (ref "R11") (pin "2") (pinfunction "2_2") (pintype "passive"))
      (node (ref "T1") (pin "2") (pinfunction "E_2") (pintype "passive"))
    )
    (net (code "34") (name "Net-(T2-B)") (class "Default")
      (node (ref "R14") (pin "2") (pinfunction "2_2") (pintype "passive"))
      (node (ref "T2") (pin "1") (pinfunction "B_1") (pintype "passive"))
    )
    (net (code "35") (name "Net-(T2-C)") (class "Default")
      (node (ref "D1") (pin "1") (pinfunction "1_1") (pintype "passive"))
      (node (ref "T2") (pin "3") (pinfunction "C_3") (pintype "passive"))
    )
    (net (code "36") (name "Net-(U1-A)") (class "Default")
      (node (ref "C4") (pin "2") (pinfunction "2_2") (pintype "passive"))
      (node (ref "U1") (pin "5") (pinfunction "A_5") (pintype "passive"))
    )
    (net (code "37") (name "Net-(U1-W)") (class "Default")
      (node (ref "C5") (pin "1") (pinfunction "1_1") (pintype "passive"))
      (node (ref "U1") (pin "6") (pinfunction "W_6") (pintype "passive"))
    )
    (net (code "38") (name "Net-(U2A-IN-)") (class "Default")
      (node (ref "R7") (pin "2") (pinfunction "2_2") (pintype "passive"))
      (node (ref "R8") (pin "2") (pinfunction "2_2") (pintype "passive"))
      (node (ref "U2") (pin "2") (pinfunction "IN-_2") (pintype "passive"))
    )
    (net (code "39") (name "Net-(U2A-OUT)") (class "Default")
      (node (ref "C4") (pin "1") (pinfunction "1_1") (pintype "passive"))
      (node (ref "R7") (pin "1") (pinfunction "1_1") (pintype "passive"))
      (node (ref "U2") (pin "1") (pinfunction "OUT_1") (pintype "passive"))
    )
    (net (code "40") (name "Net-(U2B-IN+)") (class "Default")
      (node (ref "C5") (pin "2") (pinfunction "2_2") (pintype "passive"))
      (node (ref "R1") (pin "1") (pinfunction "1_1") (pintype "passive"))
      (node (ref "U2") (pin "5") (pinfunction "IN+_5") (pintype "passive"))
    )
    (net (code "41") (name "Net-(U2B-IN-)") (class "Default")
      (node (ref "R3") (pin "2") (pinfunction "2_2") (pintype "passive"))
      (node (ref "R6") (pin "2") (pinfunction "2_2") (pintype "passive"))
      (node (ref "U2") (pin "6") (pinfunction "IN-_6") (pintype "passive"))
    )
    (net (code "42") (name "Net-(U2B-OUT)") (class "Default")
      (node (ref "C2") (pin "1") (pinfunction "1_1") (pintype "passive"))
      (node (ref "R3") (pin "1") (pinfunction "1_1") (pintype "passive"))
      (node (ref "U2") (pin "7") (pinfunction "OUT_7") (pintype "passive"))
    )
    (net (code "43") (name "Net-(U3-PA13)") (class "Default")
      (node (ref "J6") (pin "1") (pinfunction "1_1") (pintype "passive"))
      (node (ref "U3") (pin "18") (pinfunction "PA13_18") (pintype "passive"))
    )
    (net (code "44") (name "Net-(U3-PA14{slash}PA15)") (class "Default")
      (node (ref "J6") (pin "2") (pinfunction "2_2") (pintype "passive"))
      (node (ref "U3") (pin "19") (pinfunction "PA14/PA15_19") (pintype "passive"))
    )
    (net (code "45") (name "Net-(U3-PB0{slash}PB1{slash}PB2{slash}PA8)") (class "Default")
      (node (ref "R14") (pin "1") (pinfunction "1_1") (pintype "passive"))
      (node (ref "U3") (pin "15") (pinfunction "PB0/PB1/PB2/PA8_15") (pintype "passive"))
    )
    (net (code "46") (name "Net-(U3-PB9{slash}PC14)") (class "Default")
      (node (ref "U3") (pin "2") (pinfunction "PB9/PC14_2") (pintype "passive"))
      (node (ref "X1") (pin "3") (pinfunction "OUT_3") (pintype "passive"))
    )
    (net (code "47") (name "Net-(X1-HiZ)") (class "Default")
      (node (ref "R15") (pin "2") (pinfunction "2_2") (pintype "passive"))
      (node (ref "X1") (pin "1") (pinfunction "HiZ_1") (pintype "passive"))
    )
    (net (code "48") (name "unconnected-(J1-Pad3)") (class "Default")
      (node (ref "J1") (pin "3") (pinfunction "3_3") (pintype "passive+no_connect"))
    )
    (net (code "49") (name "unconnected-(J1-Pad5)") (class "Default")
      (node (ref "J1") (pin "5") (pinfunction "5_5") (pintype "passive+no_connect"))
    )
    (net (code "50") (name "unconnected-(J1-Pad7)") (class "Default")
      (node (ref "J1") (pin "7") (pinfunction "7_7") (pintype "passive+no_connect"))
    )
    (net (code "51") (name "unconnected-(J2-Pad3)") (class "Default")
      (node (ref "J2") (pin "3") (pinfunction "3_3") (pintype "passive+no_connect"))
    )
    (net (code "52") (name "unconnected-(J2-Pad5)") (class "Default")
      (node (ref "J2") (pin "5") (pinfunction "5_5") (pintype "passive+no_connect"))
    )
    (net (code "53") (name "unconnected-(J2-Pad7)") (class "Default")
      (node (ref "J2") (pin "7") (pinfunction "7_7") (pintype "passive+no_connect"))
    )
    (net (code "54") (name "unconnected-(S1-Pad9)") (class "Default")
      (node (ref "S1") (pin "9") (pinfunction "9_9") (pintype "passive+no_connect"))
    )
    (net (code "55") (name "unconnected-(U3-PA3-Pad10)") (class "Default")
      (node (ref "U3") (pin "10") (pinfunction "PA3_10") (pintype "passive+no_connect"))
    )
    (net (code "56") (name "unconnected-(U3-PA11_[PA9]-Pad16)") (class "Default")
      (node (ref "U3") (pin "16") (pinfunction "PA11_[PA9]_16") (pintype "passive+no_connect"))
    )
    (net (code "57") (name "unconnected-(U3-PA12_[PA10]-Pad17)") (class "Default")
      (node (ref "U3") (pin "17") (pinfunction "PA12_[PA10]_17") (pintype "passive+no_connect"))
    )
    (net (code "58") (name "unconnected-(U3-PB3{slash}PB4{slash}PB5{slash}PB6-Pad20)") (class "Default")
      (node (ref "U3") (pin "20") (pinfunction "PB3/PB4/PB5/PB6_20") (pintype "passive+no_connect"))
    )
    (net (code "59") (name "unconnected-(U3-PB7{slash}PB8-Pad1)") (class "Default")
      (node (ref "U3") (pin "1") (pinfunction "PB7/PB8_1") (pintype "passive+no_connect"))
    )
    (net (code "60") (name "unconnected-(U3-PC15-Pad3)") (class "Default")
      (node (ref "U3") (pin "3") (pinfunction "PC15_3") (pintype "passive+no_connect"))
    )
  )
)
